# AS_Node_Voltage_Regulators.net
KiCad netlist of a schematic drawn in Altium Designer
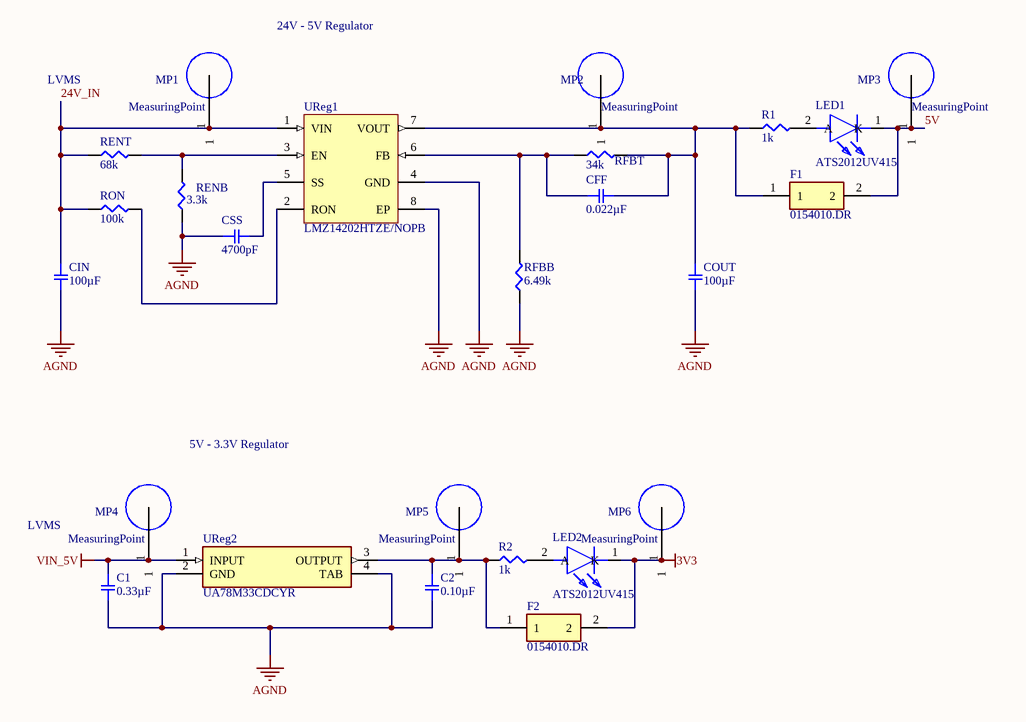
[diagram p0: AS_Node_Voltage_Regulators.SchDoc]

(export (version "E")
  (design (tool "Eeschema 10.0.6"))
  (components
    (comp (ref "C1")
      (value "0.33µF")
      (footprint "SMD-0805C")
      (description "CAP CER 0.33UF 50V X8L 0805")
      (fields
        (field (name "DIGI-KEY PART NUMBER") "490-11962-1-ND")
        (field (name "PART NUMBER") "GCM21BL81H334KA56L")
      )
      (libsource (lib "capacitor_murata_0805") (part "GCM21BL81H334KA56L"))
    )
    (comp (ref "C2")
      (value "0.10µF")
      (footprint "SMD-0805C")
      (description "CAP CER 0.1UF 50V X7R 0805")
      (fields
        (field (name "DIGI-KEY PART NUMBER") "490-11955-1-ND")
        (field (name "PART NUMBER") "GCD21BR71H104KA01L")
      )
      (libsource (lib "capacitor_murata_0805") (part "GCD21BR71H104KA01L"))
    )
    (comp (ref "CFF")
      (value "0.022µF")
      (footprint "SMD-0805C")
      (description "CAP CER 0.022UF 250V X7T 0805")
      (fields
        (field (name "DIGI-KEY PART NUMBER") "490-13988-1-ND")
        (field (name "PART NUMBER") "GC321BD72E223KX03L")
      )
      (libsource (lib "capacitor_murata_0805") (part "GC321BD72E223KX03L"))
    )
    (comp (ref "CIN")
      (value "100µF")
      (footprint "SMD:SMD-0805C")
      (description "CAP CER 100UF 2.5V X6S 0805")
      (fields
        (field (name "DIGI-KEY PART NUMBER") "490-13977-1-ND")
        (field (name "PART NUMBER") "GRM21BC80E107ME15L")
      )
      (libsource (lib "capacitor_murata_0805") (part "GRM21BC80E107ME15L"))
    )
    (comp (ref "COUT")
      (value "100µF")
      (footprint "SMD-0805C")
      (description "CAP CER 100UF 2.5V X6S 0805")
      (fields
        (field (name "DIGI-KEY PART NUMBER") "490-13977-1-ND")
        (field (name "PART NUMBER") "GRM21BC80E107ME15L")
      )
      (libsource (lib "capacitor_murata_0805") (part "GRM21BC80E107ME15L"))
    )
    (comp (ref "CSS")
      (value "4700pF")
      (footprint "SMD-0805C")
      (description "CAP CER 4700PF 250V X7R 0805")
      (fields
        (field (name "DIGI-KEY PART NUMBER") "490-5593-1-ND")
        (field (name "PART NUMBER") "GCJ21AR72E472KXJ1D")
      )
      (libsource (lib "capacitor_murata_0805") (part "GCJ21AR72E472KXJ1D"))
    )
    (comp (ref "F1")
      (value "0154010.DR")
      (footprint "SamacSys:0154001.DRT")
      (description "Fuse")
      (fields (field (name "MOUSER PART NUMBER") "576-0154010.DR") (field (name "RS PART NUMBER") "7382867"))
      (libsource (lib "*") (part "0154010.DR"))
    )
    (comp (ref "F2")
      (value "0154010.DR")
      (footprint "SamacSys:0154001.DRT")
      (description "Fuse")
      (fields (field (name "MOUSER PART NUMBER") "576-0154010.DR") (field (name "RS PART NUMBER") "7382867"))
      (libsource (lib "*") (part "0154010.DR"))
    )
    (comp (ref "LED1")
      (value "ATS2012UV415")
      (footprint "SamacSys:ATS2012UV415")
      (description "LED")
      (fields (field (name "MOUSER2 PART NUMBER") "604-ATS2012UV415"))
      (libsource (lib "*") (part "ATS2012UV415"))
    )
    (comp (ref "LED2")
      (value "ATS2012UV415")
      (footprint "SamacSys:ATS2012UV415")
      (description "LED")
      (fields (field (name "MOUSER2 PART NUMBER") "604-ATS2012UV415"))
      (libsource (lib "*") (part "ATS2012UV415"))
    )
    (comp (ref "MP1")
      (value "MeasuringPoint")
      (footprint "MeasuringPoint")
      (description "1,2mm hole for measuring purpose. Designator should be signal name.")
      (libsource (lib "MeasuringPoint") (part "MeasuringPoint"))
    )
    (comp (ref "MP2")
      (value "MeasuringPoint")
      (footprint "MeasuringPoint")
      (description "1,2mm hole for measuring purpose. Designator should be signal name.")
      (libsource (lib "MeasuringPoint") (part "MeasuringPoint"))
    )
    (comp (ref "MP3")
      (value "MeasuringPoint")
      (footprint "MeasuringPoint")
      (description "1,2mm hole for measuring purpose. Designator should be signal name.")
      (libsource (lib "MeasuringPoint") (part "MeasuringPoint"))
    )
    (comp (ref "MP4")
      (value "MeasuringPoint")
      (footprint "MeasuringPoint")
      (description "1,2mm hole for measuring purpose. Designator should be signal name.")
      (libsource (lib "MeasuringPoint") (part "MeasuringPoint"))
    )
    (comp (ref "MP5")
      (value "MeasuringPoint")
      (footprint "MeasuringPoint")
      (description "1,2mm hole for measuring purpose. Designator should be signal name.")
      (libsource (lib "MeasuringPoint") (part "MeasuringPoint"))
    )
    (comp (ref "MP6")
      (value "MeasuringPoint")
      (footprint "MeasuringPoint")
      (description "1,2mm hole for measuring purpose. Designator should be signal name.")
      (libsource (lib "MeasuringPoint") (part "MeasuringPoint"))
    )
    (comp (ref "R1")
      (value "1k")
      (footprint "SMD-0805-RES")
      (description "RES SMD 1K OHM 1% 1/8W 0805")
      (fields
        (field (name "PART NUMBER") "ERJ-6ENF1001V")
        (field (name "DIGI-KEY PART NUMBER") "P1.00KCCT-ND")
      )
      (libsource (lib "Panasonic_ERJ_0805") (part "ERJ-6ENF1001V"))
    )
    (comp (ref "R2")
      (value "1k")
      (footprint "Panasonic_ERJ_0805:SMD-0805-RES")
      (description "RES SMD 1K OHM 1% 1/8W 0805")
      (fields
        (field (name "PART NUMBER") "ERJ-6ENF1001V")
        (field (name "DIGI-KEY PART NUMBER") "P1.00KCCT-ND")
      )
      (libsource (lib "Panasonic_ERJ_0805") (part "ERJ-6ENF1001V"))
    )
    (comp (ref "RENB")
      (value "3.3k")
      (footprint "Panasonic_ERJ_0805:SMD-0805-RES")
      (description "RES SMD 3.3K OHM 1% 1/8W 0805")
      (fields
        (field (name "PART NUMBER") "ERJ-6ENF3301V")
        (field (name "DIGI-KEY PART NUMBER") "P3.30KCCT-ND")
      )
      (libsource (lib "Panasonic_ERJ_0805") (part "ERJ-6ENF3301V"))
    )
    (comp (ref "RENT")
      (value "68k")
      (footprint "Panasonic_ERJ_0805:SMD-0805-RES")
      (description "RES SMD 68K OHM 1% 1/8W 0805")
      (fields
        (field (name "PART NUMBER") "ERJ-6ENF6802V")
        (field (name "DIGI-KEY PART NUMBER") "P68.0KCCT-ND")
      )
      (libsource (lib "Panasonic_ERJ_0805") (part "ERJ-6ENF6802V"))
    )
    (comp (ref "RFBB")
      (value "6.49k")
      (footprint "Panasonic_ERJ_0805:SMD-0805-RES")
      (description "RES SMD 6.49K OHM 1% 1/8W 0805")
      (fields
        (field (name "PART NUMBER") "ERJ-6ENF6491V")
        (field (name "DIGI-KEY PART NUMBER") "P6.49KCCT-ND")
      )
      (libsource (lib "Panasonic_ERJ_0805") (part "ERJ-6ENF6491V"))
    )
    (comp (ref "RFBT")
      (value "34k")
      (footprint "Panasonic_ERJ_0805:SMD-0805-RES")
      (description "RES SMD 34K OHM 1% 1/8W 0805")
      (fields
        (field (name "PART NUMBER") "ERJ-6ENF3402V")
        (field (name "DIGI-KEY PART NUMBER") "P34.0KCCT-ND")
      )
      (libsource (lib "Panasonic_ERJ_0805") (part "ERJ-6ENF3402V"))
    )
    (comp (ref "RON")
      (value "100k")
      (footprint "Panasonic_ERJ_0805:SMD-0805-RES")
      (description "RES SMD 100K OHM 1% 1/8W 0805")
      (fields
        (field (name "PART NUMBER") "ERJ-6ENF1003V")
        (field (name "DIGI-KEY PART NUMBER") "P100KCCT-ND")
      )
      (libsource (lib "Panasonic_ERJ_0805") (part "ERJ-6ENF1003V"))
    )
    (comp (ref "UReg1")
      (value "LMZ14202HTZE/NOPB")
      (footprint "NDW0007A_V")
      (description "2A SIMPLE SWITCHER® Power Module with 42V Maximum Input, 7-pin TO-PMOD, Pb-Free, 45 Rail")
      (fields (field (name "MANUFACTURER") "Texas Instruments"))
      (libsource (lib "Altium Content Vault") (part "PM-REG-LMZ12003-8"))
    )
    (comp (ref "UReg2")
      (value "UA78M33CDCYR")
      (footprint "SamacSys:SOT230P700X180-4N")
      (description "Undefined or Miscellaneous")
      (fields (field (name "MOUSER PART NUMBER") "595-UA78M33CDCYR"))
      (libsource (lib "*") (part "UA78M33CDCYR"))
    )
  )
  (nets
    (net (code "1") (name "/5V") (class "Default")
      (node (ref "F1") (pin "2") (pinfunction "2_2") (pintype "passive"))
      (node (ref "LED1") (pin "1") (pinfunction "K_1") (pintype "passive"))
      (node (ref "MP3") (pin "1") (pinfunction "1_1") (pintype "passive"))
    )
    (net (code "2") (name "/24V_IN") (class "Default")
      (node (ref "CIN") (pin "1") (pinfunction "1_1") (pintype "passive"))
      (node (ref "MP1") (pin "1") (pinfunction "1_1") (pintype "passive"))
      (node (ref "RENT") (pin "1") (pinfunction "1_1") (pintype "passive"))
      (node (ref "RON") (pin "1") (pinfunction "1_1") (pintype "passive"))
      (node (ref "UReg1") (pin "1") (pinfunction "VIN_1") (pintype "input"))
    )
    (net (code "3") (name "3V3") (class "Default")
      (node (ref "F2") (pin "2") (pinfunction "2_2") (pintype "passive"))
      (node (ref "LED2") (pin "1") (pinfunction "K_1") (pintype "passive"))
      (node (ref "MP6") (pin "1") (pinfunction "1_1") (pintype "passive"))
    )
    (net (code "4") (name "AGND") (class "Default")
      (node (ref "C1") (pin "2") (pinfunction "2_2") (pintype "passive"))
      (node (ref "C2") (pin "2") (pinfunction "2_2") (pintype "passive"))
      (node (ref "CIN") (pin "2") (pinfunction "2_2") (pintype "passive"))
      (node (ref "COUT") (pin "2") (pinfunction "2_2") (pintype "passive"))
      (node (ref "CSS") (pin "1") (pinfunction "1_1") (pintype "passive"))
      (node (ref "RENB") (pin "1") (pinfunction "1_1") (pintype "passive"))
      (node (ref "RFBB") (pin "1") (pinfunction "1_1") (pintype "passive"))
      (node (ref "UReg1") (pin "4") (pinfunction "GND_4") (pintype "power_in"))
      (node (ref "UReg1") (pin "8") (pinfunction "EP_8") (pintype "passive"))
      (node (ref "UReg2") (pin "2") (pinfunction "GND_2") (pintype "passive"))
      (node (ref "UReg2") (pin "4") (pinfunction "TAB_4") (pintype "passive"))
    )
    (net (code "5") (name "Net-(LED1-A)") (class "Default")
      (node (ref "LED1") (pin "2") (pinfunction "A_2") (pintype "passive"))
      (node (ref "R1") (pin "2") (pinfunction "2_2") (pintype "passive"))
    )
    (net (code "6") (name "Net-(LED2-A)") (class "Default")
      (node (ref "LED2") (pin "2") (pinfunction "A_2") (pintype "passive"))
      (node (ref "R2") (pin "2") (pinfunction "2_2") (pintype "passive"))
    )
    (net (code "7") (name "Net-(UReg1-EN)") (class "Default")
      (node (ref "RENB") (pin "2") (pinfunction "2_2") (pintype "passive"))
      (node (ref "RENT") (pin "2") (pinfunction "2_2") (pintype "passive"))
      (node (ref "UReg1") (pin "3") (pinfunction "EN_3") (pintype "input"))
    )
    (net (code "8") (name "Net-(UReg1-FB)") (class "Default")
      (node (ref "CFF") (pin "1") (pinfunction "1_1") (pintype "passive"))
      (node (ref "RFBB") (pin "2") (pinfunction "2_2") (pintype "passive"))
      (node (ref "RFBT") (pin "1") (pinfunction "1_1") (pintype "passive"))
      (node (ref "UReg1") (pin "6") (pinfunction "FB_6") (pintype "input"))
    )
    (net (code "9") (name "Net-(UReg1-RON)") (class "Default")
      (node (ref "RON") (pin "2") (pinfunction "2_2") (pintype "passive"))
      (node (ref "UReg1") (pin "2") (pinfunction "RON_2") (pintype "passive"))
    )
    (net (code "10") (name "Net-(UReg1-SS)") (class "Default")
      (node (ref "CSS") (pin "2") (pinfunction "2_2") (pintype "passive"))
      (node (ref "UReg1") (pin "5") (pinfunction "SS_5") (pintype "passive"))
    )
    (net (code "11") (name "Net-(UReg1-VOUT)") (class "Default")
      (node (ref "CFF") (pin "2") (pinfunction "2_2") (pintype "passive"))
      (node (ref "COUT") (pin "1") (pinfunction "1_1") (pintype "passive"))
      (node (ref "F1") (pin "1") (pinfunction "1_1") (pintype "passive"))
      (node (ref "MP2") (pin "1") (pinfunction "1_1") (pintype "passive"))
      (node (ref "R1") (pin "1") (pinfunction "1_1") (pintype "passive"))
      (node (ref "RFBT") (pin "2") (pinfunction "2_2") (pintype "passive"))
      (node (ref "UReg1") (pin "7") (pinfunction "VOUT_7") (pintype "output"))
    )
    (net (code "12") (name "Net-(UReg2-OUTPUT)") (class "Default")
      (node (ref "C2") (pin "1") (pinfunction "1_1") (pintype "passive"))
      (node (ref "F2") (pin "1") (pinfunction "1_1") (pintype "passive"))
      (node (ref "MP5") (pin "1") (pinfunction "1_1") (pintype "passive"))
      (node (ref "R2") (pin "1") (pinfunction "1_1") (pintype "passive"))
      (node (ref "UReg2") (pin "3") (pinfunction "OUTPUT_3") (pintype "output"))
    )
    (net (code "13") (name "VIN_5V") (class "Default")
      (node (ref "C1") (pin "1") (pinfunction "1_1") (pintype "passive"))
      (node (ref "MP4") (pin "1") (pinfunction "1_1") (pintype "passive"))
      (node (ref "UReg2") (pin "1") (pinfunction "INPUT_1") (pintype "input"))
    )
  )
)
